# porcupine4v1_9.net
KiCad netlist of a schematic drawn in EAGLE
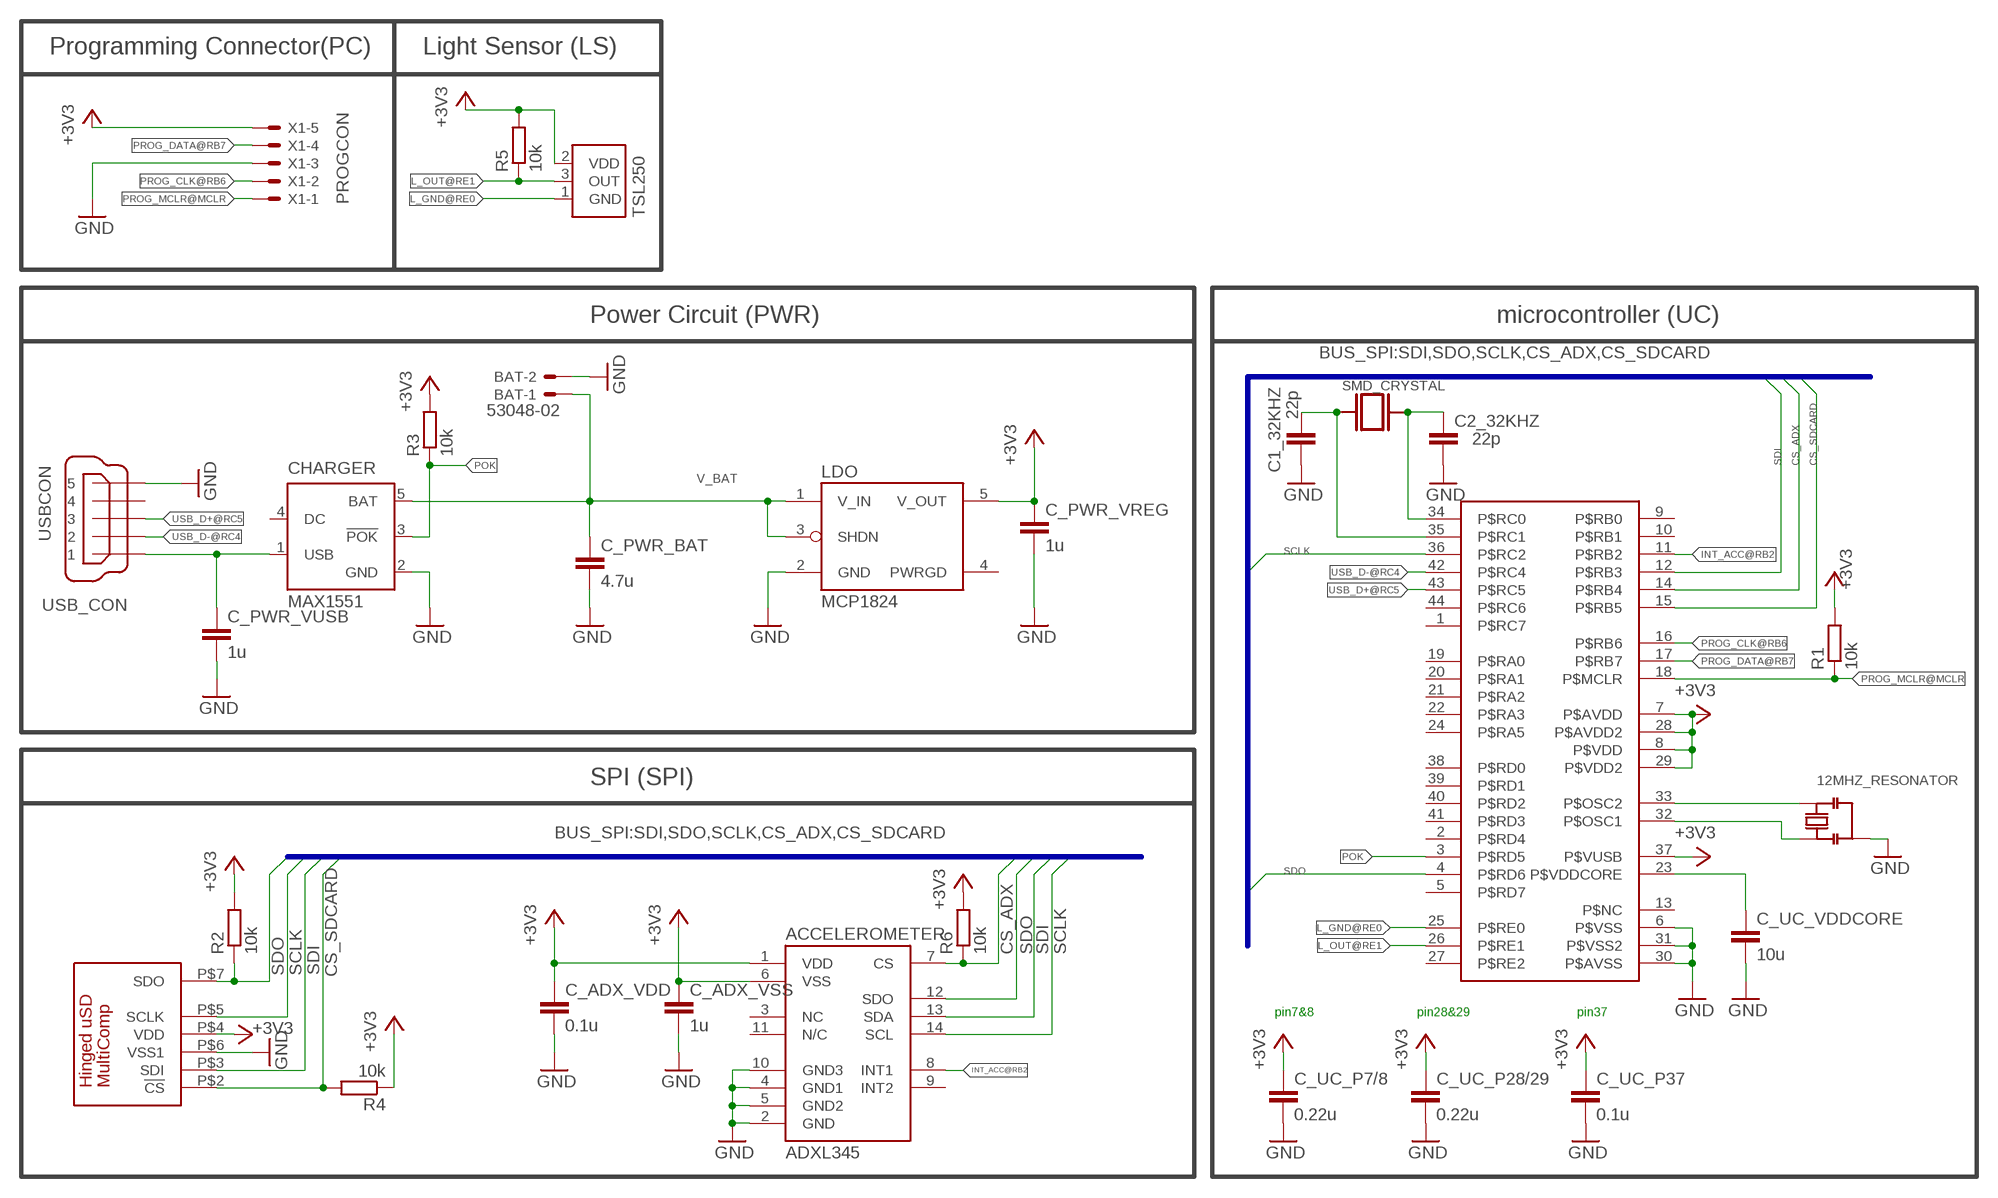
[diagram p0: schematic, sheet 1]

(export (version "E")
  (design (tool "Eeschema 10.0.6"))
  (components
    (comp (ref "12MHZ_RESONATOR")
      (value "RESONATORPRQC-C")
      (footprint "eagle-import:PRQC-C")
      (libsource (lib "eagle-import") (part "RESONATORPRQC-C"))
    )
    (comp (ref "32KHZ_CRYSTAL")
      (value "SMD_CRYSTAL")
      (footprint "eagle-import:SMD_CRYSTAL")
      (libsource (lib "eagle-import") (part "SMD_CRYSTAL"))
    )
    (comp (ref "ACCELEROMETER")
      (value "ADXL345")
      (footprint "eagle-import:LGA14")
      (libsource (lib "eagle-import") (part "ADXL345"))
    )
    (comp (ref "BAT")
      (value "53048-02")
      (footprint "eagle-import:53048-02")
      (fields (field (name "MF") "MOLEX") (field (name "MPN") "53048-0210"))
      (libsource (lib "eagle-import") (part "53?-02048"))
    )
    (comp (ref "C1_32KHZ")
      (value "22p")
      (footprint "eagle-import:C0603K")
      (libsource (lib "eagle-import") (part "C-EUC0603K"))
    )
    (comp (ref "C2_32KHZ")
      (value "22p")
      (footprint "eagle-import:C0603K")
      (libsource (lib "eagle-import") (part "C-EUC0603K"))
    )
    (comp (ref "CHARGER")
      (value "MAX1551")
      (footprint "eagle-import:SOT23-5L")
      (fields (field (name "MF") "MAXIM") (field (name "MPN") "MAX1551EZK-T"))
      (libsource (lib "eagle-import") (part "MAX1551"))
    )
    (comp (ref "C_ADX_VDD")
      (value "0.1u")
      (footprint "eagle-import:C0603K")
      (libsource (lib "eagle-import") (part "C-EUC0603K"))
    )
    (comp (ref "C_ADX_VSS")
      (value "1u")
      (footprint "eagle-import:C0603K")
      (libsource (lib "eagle-import") (part "C-EUC0603K"))
    )
    (comp (ref "C_PWR_BAT")
      (value "4.7u")
      (footprint "eagle-import:C0603K")
      (libsource (lib "eagle-import") (part "C-EUC0603K"))
    )
    (comp (ref "C_PWR_VREG")
      (value "1u")
      (footprint "eagle-import:C0603K")
      (libsource (lib "eagle-import") (part "C-EUC0603K"))
    )
    (comp (ref "C_PWR_VUSB")
      (value "1u")
      (footprint "eagle-import:C0603K")
      (libsource (lib "eagle-import") (part "C-EUC0603K"))
    )
    (comp (ref "C_UC_P7/8")
      (value "0.22u")
      (footprint "eagle-import:C0603K")
      (libsource (lib "eagle-import") (part "C-EUC0603K"))
    )
    (comp (ref "C_UC_P28/29")
      (value "0.22u")
      (footprint "eagle-import:C0603K")
      (libsource (lib "eagle-import") (part "C-EUC0603K"))
    )
    (comp (ref "C_UC_P37")
      (value "0.1u")
      (footprint "eagle-import:C0603K")
      (libsource (lib "eagle-import") (part "C-EUC0603K"))
    )
    (comp (ref "C_UC_VDDCORE")
      (value "10u")
      (footprint "eagle-import:C0805K")
      (libsource (lib "eagle-import") (part "C-EUC0805K"))
    )
    (comp (ref "LDO")
      (value "MCP1824")
      (footprint "eagle-import:SOT-23-5")
      (libsource (lib "eagle-import") (part "MCP1824"))
    )
    (comp (ref "LIGHTSENSE")
      (value "TSL250")
      (footprint "eagle-import:TSL")
      (libsource (lib "eagle-import") (part "TSL250"))
    )
    (comp (ref "PIC_CONTROLLER")
      (value "PIC_P2V6")
      (footprint "eagle-import:QFN44ML8X8")
      (libsource (lib "eagle-import") (part "PIC_P2V6"))
    )
    (comp (ref "R1")
      (value "10k")
      (footprint "eagle-import:R0603")
      (libsource (lib "eagle-import") (part "R-EU_R0603"))
    )
    (comp (ref "R2")
      (value "10k")
      (footprint "eagle-import:R0603")
      (libsource (lib "eagle-import") (part "R-EU_R0603"))
    )
    (comp (ref "R3")
      (value "10k")
      (footprint "eagle-import:R0603")
      (libsource (lib "eagle-import") (part "R-EU_R0603"))
    )
    (comp (ref "R4")
      (value "10k")
      (footprint "eagle-import:R0603")
      (libsource (lib "eagle-import") (part "R-EU_R0603"))
    )
    (comp (ref "R5")
      (value "10k")
      (footprint "eagle-import:R0603")
      (libsource (lib "eagle-import") (part "R-EU_R0603"))
    )
    (comp (ref "R6")
      (value "10k")
      (footprint "eagle-import:R0603")
      (libsource (lib "eagle-import") (part "R-EU_R0603"))
    )
    (comp (ref "SDCARD_CON")
      (value "MICROSD_CONN")
      (footprint "eagle-import:460DA40013")
      (libsource (lib "eagle-import") (part "MICROSD_CONN"))
    )
    (comp (ref "USB_CON")
      (value "USBCON")
      (footprint "eagle-import:248601")
      (libsource (lib "eagle-import") (part "USBCON"))
    )
    (comp (ref "X1")
      (value "PROGCON")
      (footprint "eagle-import:53047-05-OCT")
      (libsource (lib "eagle-import") (part "PROGCON"))
    )
  )
  (nets
    (net (code "2") (name "+3V3") (class "Default")
      (node (ref "ACCELEROMETER") (pin "1") (pinfunction "VDD_1") (pintype "bidirectional"))
      (node (ref "ACCELEROMETER") (pin "6") (pinfunction "VSS_6") (pintype "bidirectional"))
      (node (ref "C_ADX_VDD") (pin "1") (pinfunction "1_1") (pintype "passive"))
      (node (ref "C_ADX_VSS") (pin "1") (pinfunction "1_1") (pintype "passive"))
      (node (ref "C_PWR_VREG") (pin "1") (pinfunction "1_1") (pintype "passive"))
      (node (ref "C_UC_P28/29") (pin "1") (pinfunction "1_1") (pintype "passive"))
      (node (ref "C_UC_P37") (pin "1") (pinfunction "1_1") (pintype "passive"))
      (node (ref "C_UC_P7/8") (pin "1") (pinfunction "1_1") (pintype "passive"))
      (node (ref "LDO") (pin "5") (pinfunction "V_OUT_5") (pintype "bidirectional"))
      (node (ref "LIGHTSENSE") (pin "2") (pinfunction "VDD_2") (pintype "power_in"))
      (node (ref "PIC_CONTROLLER") (pin "28") (pinfunction "P$AVDD2_28") (pintype "bidirectional"))
      (node (ref "PIC_CONTROLLER") (pin "29") (pinfunction "P$VDD2_29") (pintype "bidirectional"))
      (node (ref "PIC_CONTROLLER") (pin "37") (pinfunction "P$VUSB_37") (pintype "bidirectional"))
      (node (ref "PIC_CONTROLLER") (pin "7") (pinfunction "P$AVDD_7") (pintype "input"))
      (node (ref "PIC_CONTROLLER") (pin "8") (pinfunction "P$VDD_8") (pintype "bidirectional"))
      (node (ref "R1") (pin "2") (pinfunction "2_2") (pintype "passive"))
      (node (ref "R2") (pin "2") (pinfunction "2_2") (pintype "passive"))
      (node (ref "R3") (pin "2") (pinfunction "2_2") (pintype "passive"))
      (node (ref "R4") (pin "1") (pinfunction "1_1") (pintype "passive"))
      (node (ref "R5") (pin "2") (pinfunction "2_2") (pintype "passive"))
      (node (ref "R6") (pin "2") (pinfunction "2_2") (pintype "passive"))
      (node (ref "SDCARD_CON") (pin "P$4") (pinfunction "VDD_P$4") (pintype "bidirectional"))
      (node (ref "X1") (pin "5") (pinfunction "S_5") (pintype "passive"))
    )
    (net (code "3") (name "/CS_ADX") (class "Default")
      (node (ref "ACCELEROMETER") (pin "7") (pinfunction "CS_7") (pintype "bidirectional"))
      (node (ref "PIC_CONTROLLER") (pin "14") (pinfunction "P$RB4_14") (pintype "bidirectional"))
      (node (ref "R6") (pin "1") (pinfunction "1_1") (pintype "passive"))
    )
    (net (code "4") (name "/CS_SDCARD") (class "Default")
      (node (ref "PIC_CONTROLLER") (pin "15") (pinfunction "P$RB5_15") (pintype "bidirectional"))
      (node (ref "R4") (pin "2") (pinfunction "2_2") (pintype "passive"))
      (node (ref "SDCARD_CON") (pin "P$2") (pinfunction "~{CS}_P$2") (pintype "bidirectional"))
    )
    (net (code "5") (name "/P$RD7") (class "Default")
      (node (ref "PIC_CONTROLLER") (pin "5") (pinfunction "P$RD7_5") (pintype "power_in"))
    )
    (net (code "6") (name "/SCLK") (class "Default")
      (node (ref "ACCELEROMETER") (pin "14") (pinfunction "SCL_14") (pintype "bidirectional"))
      (node (ref "PIC_CONTROLLER") (pin "36") (pinfunction "P$RC2_36") (pintype "bidirectional"))
      (node (ref "SDCARD_CON") (pin "P$5") (pinfunction "SCLK_P$5") (pintype "bidirectional"))
    )
    (net (code "7") (name "/SDI") (class "Default")
      (node (ref "ACCELEROMETER") (pin "13") (pinfunction "SDA_13") (pintype "bidirectional"))
      (node (ref "PIC_CONTROLLER") (pin "12") (pinfunction "P$RB3_12") (pintype "bidirectional"))
      (node (ref "SDCARD_CON") (pin "P$3") (pinfunction "SDI_P$3") (pintype "bidirectional"))
    )
    (net (code "8") (name "/SDO") (class "Default")
      (node (ref "ACCELEROMETER") (pin "12") (pinfunction "SDO_12") (pintype "bidirectional"))
      (node (ref "PIC_CONTROLLER") (pin "4") (pinfunction "P$RD6_4") (pintype "bidirectional"))
      (node (ref "R2") (pin "1") (pinfunction "1_1") (pintype "passive"))
      (node (ref "SDCARD_CON") (pin "P$7") (pinfunction "SDO_P$7") (pintype "bidirectional"))
    )
    (net (code "9") (name "/V_BAT") (class "Default")
      (node (ref "BAT") (pin "1") (pinfunction "S_1") (pintype "passive"))
      (node (ref "CHARGER") (pin "5") (pinfunction "BAT_5") (pintype "passive"))
      (node (ref "C_PWR_BAT") (pin "1") (pinfunction "1_1") (pintype "passive"))
      (node (ref "LDO") (pin "1") (pinfunction "V_IN_1") (pintype "bidirectional"))
      (node (ref "LDO") (pin "3") (pinfunction "SHDN_3") (pintype "bidirectional"))
    )
    (net (code "11") (name "GND") (class "Default")
      (node (ref "12MHZ_RESONATOR") (pin "2_GND") (pinfunction "GND_2_GND") (pintype "bidirectional"))
      (node (ref "ACCELEROMETER") (pin "10") (pinfunction "GND3_10") (pintype "bidirectional"))
      (node (ref "ACCELEROMETER") (pin "2") (pinfunction "GND_2") (pintype "bidirectional"))
      (node (ref "ACCELEROMETER") (pin "4") (pinfunction "GND1_4") (pintype "bidirectional"))
      (node (ref "ACCELEROMETER") (pin "5") (pinfunction "GND2_5") (pintype "bidirectional"))
      (node (ref "BAT") (pin "2") (pinfunction "S_2") (pintype "passive"))
      (node (ref "C1_32KHZ") (pin "2") (pinfunction "2_2") (pintype "passive"))
      (node (ref "C2_32KHZ") (pin "2") (pinfunction "2_2") (pintype "passive"))
      (node (ref "CHARGER") (pin "2") (pinfunction "GND_2") (pintype "power_in"))
      (node (ref "C_ADX_VDD") (pin "2") (pinfunction "2_2") (pintype "passive"))
      (node (ref "C_ADX_VSS") (pin "2") (pinfunction "2_2") (pintype "passive"))
      (node (ref "C_PWR_BAT") (pin "2") (pinfunction "2_2") (pintype "passive"))
      (node (ref "C_PWR_VREG") (pin "2") (pinfunction "2_2") (pintype "passive"))
      (node (ref "C_PWR_VUSB") (pin "2") (pinfunction "2_2") (pintype "passive"))
      (node (ref "C_UC_P28/29") (pin "2") (pinfunction "2_2") (pintype "passive"))
      (node (ref "C_UC_P37") (pin "2") (pinfunction "2_2") (pintype "passive"))
      (node (ref "C_UC_P7/8") (pin "2") (pinfunction "2_2") (pintype "passive"))
      (node (ref "C_UC_VDDCORE") (pin "2") (pinfunction "2_2") (pintype "passive"))
      (node (ref "LDO") (pin "2") (pinfunction "GND_2") (pintype "bidirectional"))
      (node (ref "PIC_CONTROLLER") (pin "30") (pinfunction "P$AVSS_30") (pintype "input"))
      (node (ref "PIC_CONTROLLER") (pin "31") (pinfunction "P$VSS2_31") (pintype "output"))
      (node (ref "PIC_CONTROLLER") (pin "6") (pinfunction "P$VSS_6") (pintype "input"))
      (node (ref "SDCARD_CON") (pin "P$6") (pinfunction "VSS1_P$6") (pintype "bidirectional"))
      (node (ref "USB_CON") (pin "5") (pinfunction "5_5") (pintype "input"))
      (node (ref "X1") (pin "3") (pinfunction "S_3") (pintype "passive"))
    )
    (net (code "12") (name "INT_ACC@RB2") (class "Default")
      (node (ref "ACCELEROMETER") (pin "8") (pinfunction "INT1_8") (pintype "bidirectional"))
      (node (ref "PIC_CONTROLLER") (pin "11") (pinfunction "P$RB2_11") (pintype "power_in"))
    )
    (net (code "13") (name "L_GND@RE0") (class "Default")
      (node (ref "LIGHTSENSE") (pin "1") (pinfunction "GND_1") (pintype "power_in"))
      (node (ref "PIC_CONTROLLER") (pin "25") (pinfunction "P$RE0_25") (pintype "bidirectional"))
    )
    (net (code "14") (name "L_OUT@RE1") (class "Default")
      (node (ref "LIGHTSENSE") (pin "3") (pinfunction "OUT_3") (pintype "output"))
      (node (ref "PIC_CONTROLLER") (pin "26") (pinfunction "P$RE1_26") (pintype "input"))
      (node (ref "R5") (pin "1") (pinfunction "1_1") (pintype "passive"))
    )
    (net (code "15") (name "Net-(12MHZ_RESONATOR-2)") (class "Default")
      (node (ref "12MHZ_RESONATOR") (pin "3") (pinfunction "2_3") (pintype "bidirectional"))
      (node (ref "PIC_CONTROLLER") (pin "32") (pinfunction "P$OSC1_32") (pintype "bidirectional"))
    )
    (net (code "16") (name "Net-(32KHZ_CRYSTAL-1)") (class "Default")
      (node (ref "32KHZ_CRYSTAL") (pin "P$1") (pinfunction "1_P$1") (pintype "passive"))
      (node (ref "C1_32KHZ") (pin "1") (pinfunction "1_1") (pintype "passive"))
      (node (ref "PIC_CONTROLLER") (pin "35") (pinfunction "P$RC1_35") (pintype "bidirectional"))
    )
    (net (code "17") (name "Net-(32KHZ_CRYSTAL-2)") (class "Default")
      (node (ref "32KHZ_CRYSTAL") (pin "P$2") (pinfunction "2_P$2") (pintype "passive"))
      (node (ref "C2_32KHZ") (pin "1") (pinfunction "1_1") (pintype "passive"))
      (node (ref "PIC_CONTROLLER") (pin "34") (pinfunction "P$RC0_34") (pintype "bidirectional"))
    )
    (net (code "18") (name "Net-(CHARGER-USB)") (class "Default")
      (node (ref "CHARGER") (pin "1") (pinfunction "USB_1") (pintype "input"))
      (node (ref "C_PWR_VUSB") (pin "1") (pinfunction "1_1") (pintype "passive"))
      (node (ref "USB_CON") (pin "1") (pinfunction "1_1") (pintype "input"))
    )
    (net (code "19") (name "Net-(PIC_CONTROLLER-P$OSC2)") (class "Default")
      (node (ref "12MHZ_RESONATOR") (pin "1") (pinfunction "1_1") (pintype "bidirectional"))
      (node (ref "PIC_CONTROLLER") (pin "33") (pinfunction "P$OSC2_33") (pintype "bidirectional"))
    )
    (net (code "20") (name "Net-(PIC_CONTROLLER-P$VDDCORE)") (class "Default")
      (node (ref "C_UC_VDDCORE") (pin "1") (pinfunction "1_1") (pintype "passive"))
      (node (ref "PIC_CONTROLLER") (pin "23") (pinfunction "P$VDDCORE_23") (pintype "bidirectional"))
    )
    (net (code "21") (name "POK") (class "Default")
      (node (ref "CHARGER") (pin "3") (pinfunction "~{POK}_3") (pintype "output"))
      (node (ref "PIC_CONTROLLER") (pin "3") (pinfunction "P$RD5_3") (pintype "power_in"))
      (node (ref "R3") (pin "1") (pinfunction "1_1") (pintype "passive"))
    )
    (net (code "22") (name "PROG_CLK@RB6") (class "Default")
      (node (ref "PIC_CONTROLLER") (pin "16") (pinfunction "P$RB6_16") (pintype "power_in"))
      (node (ref "X1") (pin "2") (pinfunction "S_2") (pintype "passive"))
    )
    (net (code "23") (name "PROG_DATA@RB7") (class "Default")
      (node (ref "PIC_CONTROLLER") (pin "17") (pinfunction "P$RB7_17") (pintype "power_in"))
      (node (ref "X1") (pin "4") (pinfunction "S_4") (pintype "passive"))
    )
    (net (code "24") (name "PROG_MCLR@MCLR") (class "Default")
      (node (ref "PIC_CONTROLLER") (pin "18") (pinfunction "P$MCLR_18") (pintype "input"))
      (node (ref "R1") (pin "1") (pinfunction "1_1") (pintype "passive"))
      (node (ref "X1") (pin "1") (pinfunction "S_1") (pintype "passive"))
    )
    (net (code "25") (name "USB_D+@RC5") (class "Default")
      (node (ref "PIC_CONTROLLER") (pin "43") (pinfunction "P$RC5_43") (pintype "bidirectional"))
      (node (ref "USB_CON") (pin "3") (pinfunction "3_3") (pintype "input"))
    )
    (net (code "26") (name "USB_D-@RC4") (class "Default")
      (node (ref "PIC_CONTROLLER") (pin "42") (pinfunction "P$RC4_42") (pintype "bidirectional"))
      (node (ref "USB_CON") (pin "2") (pinfunction "2_2") (pintype "input"))
    )
    (net (code "27") (name "unconnected-(ACCELEROMETER-INT2-Pad9)") (class "Default")
      (node (ref "ACCELEROMETER") (pin "9") (pinfunction "INT2_9") (pintype "bidirectional"))
    )
    (net (code "28") (name "unconnected-(ACCELEROMETER-NC-Pad3)") (class "Default")
      (node (ref "ACCELEROMETER") (pin "3") (pinfunction "NC_3") (pintype "bidirectional"))
    )
    (net (code "29") (name "unconnected-(ACCELEROMETER-N{slash}C-Pad11)") (class "Default")
      (node (ref "ACCELEROMETER") (pin "11") (pinfunction "N/C_11") (pintype "bidirectional"))
    )
    (net (code "30") (name "unconnected-(CHARGER-DC-Pad4)") (class "Default")
      (node (ref "CHARGER") (pin "4") (pinfunction "DC_4") (pintype "input"))
    )
    (net (code "31") (name "unconnected-(LDO-PWRGD-Pad4)") (class "Default")
      (node (ref "LDO") (pin "4") (pinfunction "PWRGD_4") (pintype "bidirectional"))
    )
    (net (code "32") (name "unconnected-(PIC_CONTROLLER-P$NC-Pad13)") (class "Default")
      (node (ref "PIC_CONTROLLER") (pin "13") (pinfunction "P$NC_13") (pintype "bidirectional"))
    )
    (net (code "33") (name "unconnected-(PIC_CONTROLLER-P$RA0-Pad19)") (class "Default")
      (node (ref "PIC_CONTROLLER") (pin "19") (pinfunction "P$RA0_19") (pintype "bidirectional"))
    )
    (net (code "34") (name "unconnected-(PIC_CONTROLLER-P$RA1-Pad20)") (class "Default")
      (node (ref "PIC_CONTROLLER") (pin "20") (pinfunction "P$RA1_20") (pintype "bidirectional"))
    )
    (net (code "35") (name "unconnected-(PIC_CONTROLLER-P$RA2-Pad21)") (class "Default")
      (node (ref "PIC_CONTROLLER") (pin "21") (pinfunction "P$RA2_21") (pintype "bidirectional"))
    )
    (net (code "36") (name "unconnected-(PIC_CONTROLLER-P$RA3-Pad22)") (class "Default")
      (node (ref "PIC_CONTROLLER") (pin "22") (pinfunction "P$RA3_22") (pintype "bidirectional"))
    )
    (net (code "37") (name "unconnected-(PIC_CONTROLLER-P$RA5-Pad24)") (class "Default")
      (node (ref "PIC_CONTROLLER") (pin "24") (pinfunction "P$RA5_24") (pintype "bidirectional"))
    )
    (net (code "38") (name "unconnected-(PIC_CONTROLLER-P$RB0-Pad9)") (class "Default")
      (node (ref "PIC_CONTROLLER") (pin "9") (pinfunction "P$RB0_9") (pintype "bidirectional"))
    )
    (net (code "39") (name "unconnected-(PIC_CONTROLLER-P$RB1-Pad10)") (class "Default")
      (node (ref "PIC_CONTROLLER") (pin "10") (pinfunction "P$RB1_10") (pintype "bidirectional"))
    )
    (net (code "40") (name "unconnected-(PIC_CONTROLLER-P$RC6-Pad44)") (class "Default")
      (node (ref "PIC_CONTROLLER") (pin "44") (pinfunction "P$RC6_44") (pintype "bidirectional"))
    )
    (net (code "41") (name "unconnected-(PIC_CONTROLLER-P$RC7-Pad1)") (class "Default")
      (node (ref "PIC_CONTROLLER") (pin "1") (pinfunction "P$RC7_1") (pintype "bidirectional"))
    )
    (net (code "42") (name "unconnected-(PIC_CONTROLLER-P$RD0-Pad38)") (class "Default")
      (node (ref "PIC_CONTROLLER") (pin "38") (pinfunction "P$RD0_38") (pintype "bidirectional"))
    )
    (net (code "43") (name "unconnected-(PIC_CONTROLLER-P$RD1-Pad39)") (class "Default")
      (node (ref "PIC_CONTROLLER") (pin "39") (pinfunction "P$RD1_39") (pintype "bidirectional"))
    )
    (net (code "44") (name "unconnected-(PIC_CONTROLLER-P$RD2-Pad40)") (class "Default")
      (node (ref "PIC_CONTROLLER") (pin "40") (pinfunction "P$RD2_40") (pintype "bidirectional"))
    )
    (net (code "45") (name "unconnected-(PIC_CONTROLLER-P$RD3-Pad41)") (class "Default")
      (node (ref "PIC_CONTROLLER") (pin "41") (pinfunction "P$RD3_41") (pintype "bidirectional"))
    )
    (net (code "46") (name "unconnected-(PIC_CONTROLLER-P$RD4-Pad2)") (class "Default")
      (node (ref "PIC_CONTROLLER") (pin "2") (pinfunction "P$RD4_2") (pintype "bidirectional"))
    )
    (net (code "47") (name "unconnected-(PIC_CONTROLLER-P$RE2-Pad27)") (class "Default")
      (node (ref "PIC_CONTROLLER") (pin "27") (pinfunction "P$RE2_27") (pintype "bidirectional"))
    )
    (net (code "48") (name "unconnected-(USB_CON-Pad4)") (class "Default")
      (node (ref "USB_CON") (pin "4") (pinfunction "4_4") (pintype "input"))
    )
  )
)
